# CNC-CTRL-BRD-Simple.net
KiCad netlist of a schematic drawn in EAGLE
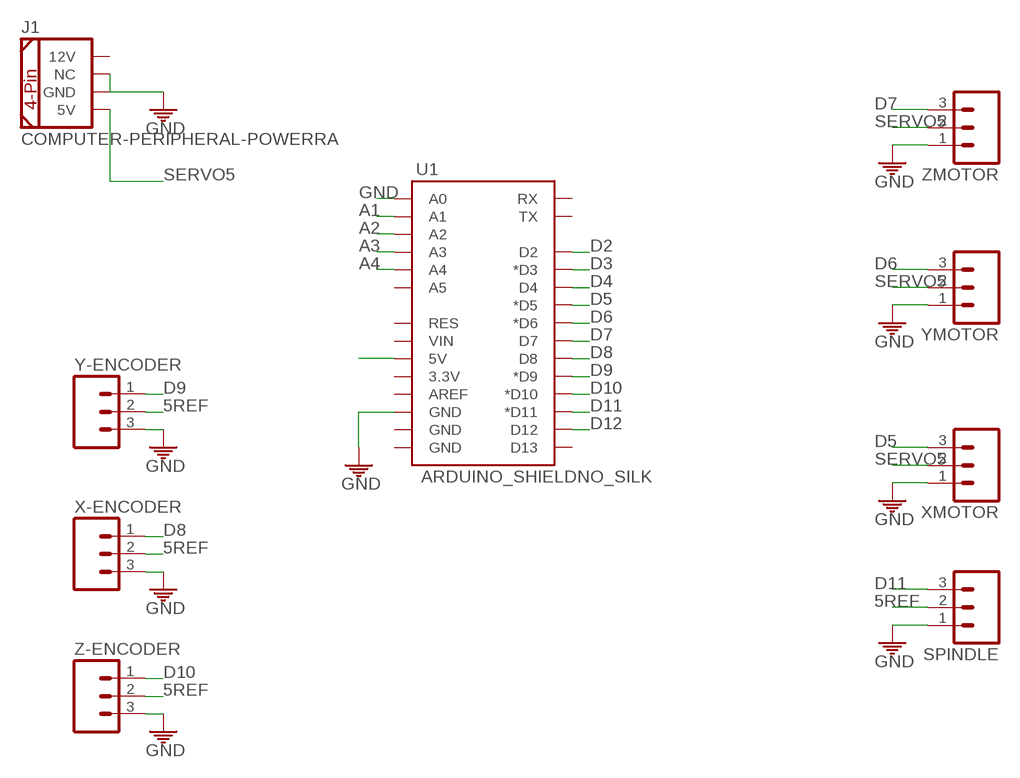
[diagram p0: schematic, sheet 1]

(export (version "E")
  (design (tool "Eeschema 10.0.6"))
  (components
    (comp (ref "J1")
      (value "COMPUTER-PERIPHERAL-POWERRA")
      (footprint "eagle-import:COMPUTER-PERIPHERAL-POWER-RA")
      (libsource (lib "eagle-import") (part "COMPUTER-PERIPHERAL-POWERRA"))
    )
    (comp (ref "SPINDLE")
      (value "M03LOCK")
      (footprint "eagle-import:1X03_LOCK")
      (libsource (lib "eagle-import") (part "M03LOCK"))
    )
    (comp (ref "U1")
      (value "ARDUINO_SHIELDNO_SILK")
      (footprint "eagle-import:DUEMILANOVE_VIAS")
      (libsource (lib "eagle-import") (part "ARDUINO_SHIELDNO_SILK"))
    )
    (comp (ref "X-ENCODER")
      (value "M03LOCK")
      (footprint "eagle-import:1X03_LOCK")
      (libsource (lib "eagle-import") (part "M03LOCK"))
    )
    (comp (ref "XMOTOR")
      (value "M03LOCK")
      (footprint "eagle-import:1X03_LOCK")
      (libsource (lib "eagle-import") (part "M03LOCK"))
    )
    (comp (ref "Y-ENCODER")
      (value "M03LOCK")
      (footprint "eagle-import:1X03_LOCK")
      (libsource (lib "eagle-import") (part "M03LOCK"))
    )
    (comp (ref "YMOTOR")
      (value "M03LOCK")
      (footprint "eagle-import:1X03_LOCK")
      (libsource (lib "eagle-import") (part "M03LOCK"))
    )
    (comp (ref "Z-ENCODER")
      (value "M03LOCK")
      (footprint "eagle-import:1X03_LOCK")
      (libsource (lib "eagle-import") (part "M03LOCK"))
    )
    (comp (ref "ZMOTOR")
      (value "M03LOCK")
      (footprint "eagle-import:1X03_LOCK")
      (libsource (lib "eagle-import") (part "M03LOCK"))
    )
  )
  (nets
    (net (code "1") (name "/5REF") (class "Default")
      (node (ref "SPINDLE") (pin "2") (pinfunction "2_2") (pintype "passive"))
      (node (ref "U1") (pin "5V") (pinfunction "5V_5V") (pintype "bidirectional"))
      (node (ref "X-ENCODER") (pin "2") (pinfunction "2_2") (pintype "passive"))
      (node (ref "Y-ENCODER") (pin "2") (pinfunction "2_2") (pintype "passive"))
      (node (ref "Z-ENCODER") (pin "2") (pinfunction "2_2") (pintype "passive"))
    )
    (net (code "2") (name "/A1") (class "Default")
      (node (ref "U1") (pin "A1") (pinfunction "A1_A1") (pintype "bidirectional"))
    )
    (net (code "3") (name "/A2") (class "Default")
      (node (ref "U1") (pin "A2") (pinfunction "A2_A2") (pintype "bidirectional"))
    )
    (net (code "4") (name "/A3") (class "Default")
      (node (ref "U1") (pin "A3") (pinfunction "A3_A3") (pintype "bidirectional"))
    )
    (net (code "5") (name "/A4") (class "Default")
      (node (ref "U1") (pin "A4") (pinfunction "A4_A4") (pintype "bidirectional"))
    )
    (net (code "6") (name "/D2") (class "Default")
      (node (ref "U1") (pin "D2") (pinfunction "D2_D2") (pintype "bidirectional"))
    )
    (net (code "7") (name "/D3") (class "Default")
      (node (ref "U1") (pin "D3") (pinfunction "*D3_D3") (pintype "bidirectional"))
    )
    (net (code "8") (name "/D4") (class "Default")
      (node (ref "U1") (pin "D4") (pinfunction "D4_D4") (pintype "bidirectional"))
    )
    (net (code "9") (name "/D5") (class "Default")
      (node (ref "U1") (pin "D5") (pinfunction "*D5_D5") (pintype "bidirectional"))
      (node (ref "XMOTOR") (pin "3") (pinfunction "3_3") (pintype "passive"))
    )
    (net (code "10") (name "/D6") (class "Default")
      (node (ref "U1") (pin "D6") (pinfunction "*D6_D6") (pintype "bidirectional"))
      (node (ref "YMOTOR") (pin "3") (pinfunction "3_3") (pintype "passive"))
    )
    (net (code "11") (name "/D7") (class "Default")
      (node (ref "U1") (pin "D7") (pinfunction "D7_D7") (pintype "bidirectional"))
      (node (ref "ZMOTOR") (pin "3") (pinfunction "3_3") (pintype "passive"))
    )
    (net (code "12") (name "/D8") (class "Default")
      (node (ref "U1") (pin "D8") (pinfunction "D8_D8") (pintype "bidirectional"))
      (node (ref "X-ENCODER") (pin "1") (pinfunction "1_1") (pintype "passive"))
    )
    (net (code "13") (name "/D9") (class "Default")
      (node (ref "U1") (pin "D9") (pinfunction "*D9_D9") (pintype "bidirectional"))
      (node (ref "Y-ENCODER") (pin "1") (pinfunction "1_1") (pintype "passive"))
    )
    (net (code "14") (name "/D10") (class "Default")
      (node (ref "U1") (pin "D10") (pinfunction "*D10_D10") (pintype "bidirectional"))
      (node (ref "Z-ENCODER") (pin "1") (pinfunction "1_1") (pintype "passive"))
    )
    (net (code "15") (name "/D11") (class "Default")
      (node (ref "SPINDLE") (pin "3") (pinfunction "3_3") (pintype "passive"))
      (node (ref "U1") (pin "D11") (pinfunction "*D11_D11") (pintype "bidirectional"))
    )
    (net (code "16") (name "/D12") (class "Default")
      (node (ref "U1") (pin "D12") (pinfunction "D12_D12") (pintype "bidirectional"))
    )
    (net (code "17") (name "/SERVO5") (class "Default")
      (node (ref "J1") (pin "5V") (pinfunction "5V_5V") (pintype "passive"))
      (node (ref "XMOTOR") (pin "2") (pinfunction "2_2") (pintype "passive"))
      (node (ref "YMOTOR") (pin "2") (pinfunction "2_2") (pintype "passive"))
      (node (ref "ZMOTOR") (pin "2") (pinfunction "2_2") (pintype "passive"))
    )
    (net (code "18") (name "GND") (class "Default")
      (node (ref "J1") (pin "GND") (pinfunction "GND_GND") (pintype "passive"))
      (node (ref "J1") (pin "NC") (pinfunction "NC_NC") (pintype "passive"))
      (node (ref "SPINDLE") (pin "1") (pinfunction "1_1") (pintype "passive"))
      (node (ref "U1") (pin "A0") (pinfunction "A0_A0") (pintype "bidirectional"))
      (node (ref "U1") (pin "GND@2") (pinfunction "GND_GND@2") (pintype "bidirectional"))
      (node (ref "X-ENCODER") (pin "3") (pinfunction "3_3") (pintype "passive"))
      (node (ref "XMOTOR") (pin "1") (pinfunction "1_1") (pintype "passive"))
      (node (ref "Y-ENCODER") (pin "3") (pinfunction "3_3") (pintype "passive"))
      (node (ref "YMOTOR") (pin "1") (pinfunction "1_1") (pintype "passive"))
      (node (ref "Z-ENCODER") (pin "3") (pinfunction "3_3") (pintype "passive"))
      (node (ref "ZMOTOR") (pin "1") (pinfunction "1_1") (pintype "passive"))
    )
    (net (code "19") (name "unconnected-(J1-Pad12V)") (class "Default")
      (node (ref "J1") (pin "12V") (pinfunction "12V_12V") (pintype "passive"))
    )
    (net (code "20") (name "unconnected-(U1-GND-PadGND@0)") (class "Default")
      (node (ref "U1") (pin "GND@0") (pinfunction "GND_GND@0") (pintype "bidirectional"))
    )
    (net (code "21") (name "unconnected-(U1-GND-PadGND@1)") (class "Default")
      (node (ref "U1") (pin "GND@1") (pinfunction "GND_GND@1") (pintype "bidirectional"))
    )
    (net (code "22") (name "unconnected-(U1-Pad3.3V)") (class "Default")
      (node (ref "U1") (pin "3.3V") (pinfunction "3.3V_3.3V") (pintype "bidirectional"))
    )
    (net (code "23") (name "unconnected-(U1-PadA5)") (class "Default")
      (node (ref "U1") (pin "A5") (pinfunction "A5_A5") (pintype "bidirectional"))
    )
    (net (code "24") (name "unconnected-(U1-PadAREF)") (class "Default")
      (node (ref "U1") (pin "AREF") (pinfunction "AREF_AREF") (pintype "bidirectional"))
    )
    (net (code "25") (name "unconnected-(U1-PadD13)") (class "Default")
      (node (ref "U1") (pin "D13") (pinfunction "D13_D13") (pintype "bidirectional"))
    )
    (net (code "26") (name "unconnected-(U1-PadRES)") (class "Default")
      (node (ref "U1") (pin "RES") (pinfunction "RES_RES") (pintype "bidirectional"))
    )
    (net (code "27") (name "unconnected-(U1-PadRX)") (class "Default")
      (node (ref "U1") (pin "RX") (pinfunction "RX_RX") (pintype "bidirectional"))
    )
    (net (code "28") (name "unconnected-(U1-PadTX)") (class "Default")
      (node (ref "U1") (pin "TX") (pinfunction "TX_TX") (pintype "bidirectional"))
    )
    (net (code "29") (name "unconnected-(U1-PadVIN)") (class "Default")
      (node (ref "U1") (pin "VIN") (pinfunction "VIN_VIN") (pintype "bidirectional"))
    )
  )
)
